# Power_supply.net
KiCad netlist of a schematic drawn in Altium Designer
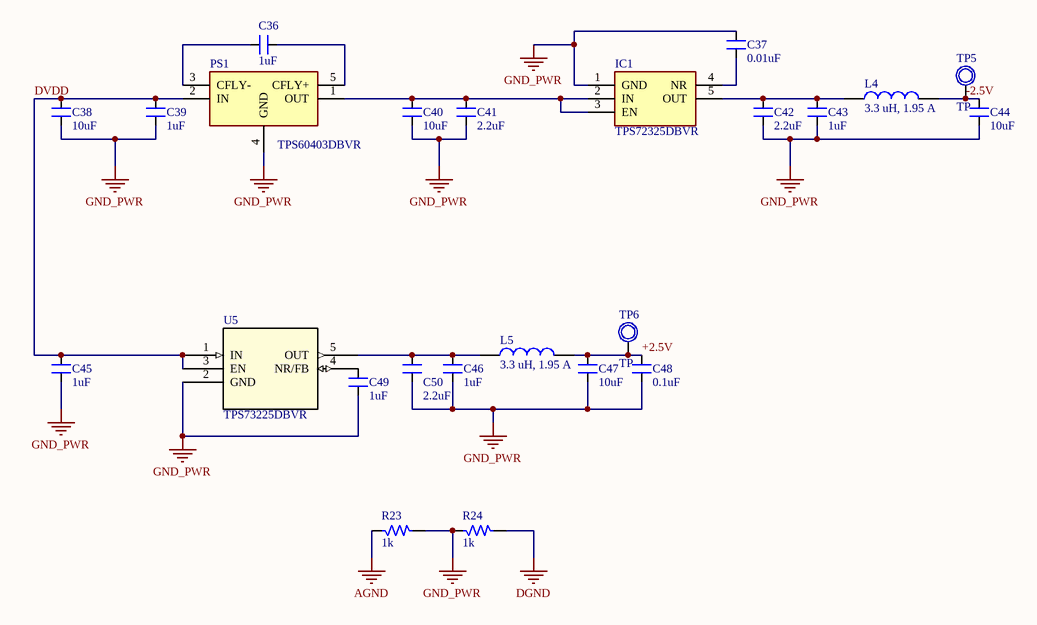
[diagram p0: Power supply.SchDoc]

(export (version "E")
  (design (tool "Eeschema 10.0.6"))
  (components
    (comp (ref "C36")
      (value "1uF")
      (footprint "SM-0805")
      (description "Cap SMD")
      (libsource (lib "VioletofSun") (part "CM"))
    )
    (comp (ref "C37")
      (value "0.01uF")
      (footprint "SM-0805")
      (description "Cap SMD")
      (libsource (lib "VioletofSun") (part "CM"))
    )
    (comp (ref "C38")
      (value "10uF")
      (footprint "SM-0805")
      (description "Cap SMD")
      (libsource (lib "VioletofSun") (part "CM"))
    )
    (comp (ref "C39")
      (value "1uF")
      (footprint "SM-0805")
      (description "Cap SMD")
      (libsource (lib "VioletofSun") (part "CM"))
    )
    (comp (ref "C40")
      (value "10uF")
      (footprint "SM-0805")
      (description "Cap SMD")
      (libsource (lib "VioletofSun") (part "CM"))
    )
    (comp (ref "C41")
      (value "2.2uF")
      (footprint "SM-0805")
      (description "Cap SMD")
      (libsource (lib "VioletofSun") (part "CM"))
    )
    (comp (ref "C42")
      (value "2.2uF")
      (footprint "SM-0805")
      (description "Cap SMD")
      (libsource (lib "VioletofSun") (part "CM"))
    )
    (comp (ref "C43")
      (value "1uF")
      (footprint "SM-0805")
      (description "Cap SMD")
      (libsource (lib "VioletofSun") (part "CM"))
    )
    (comp (ref "C44")
      (value "10uF")
      (footprint "SM-0805")
      (description "Cap SMD")
      (libsource (lib "VioletofSun") (part "CM"))
    )
    (comp (ref "C45")
      (value "1uF")
      (footprint "SM-0805")
      (description "Cap SMD")
      (libsource (lib "VioletofSun") (part "CM"))
    )
    (comp (ref "C46")
      (value "1uF")
      (footprint "SM-0805")
      (description "Cap SMD")
      (libsource (lib "VioletofSun") (part "CM"))
    )
    (comp (ref "C47")
      (value "10uF")
      (footprint "SM-0805")
      (description "Cap SMD")
      (libsource (lib "VioletofSun") (part "CM"))
    )
    (comp (ref "C48")
      (value "0.1uF")
      (footprint "SM-0805")
      (description "Cap SMD")
      (libsource (lib "VioletofSun") (part "CM"))
    )
    (comp (ref "C49")
      (value "1uF")
      (footprint "SM-0805")
      (description "Cap SMD")
      (libsource (lib "VioletofSun") (part "CM"))
    )
    (comp (ref "C50")
      (value "2.2uF")
      (footprint "SM-0805")
      (description "Cap SMD")
      (libsource (lib "VioletofSun") (part "CM"))
    )
    (comp (ref "IC1")
      (value "TPS72325DBVR")
      (footprint "SamacSys:SOT95P280X145-5N")
      (description "Integrated Circuit")
      (fields (field (name "MOUSER PART NUMBER") "595-TPS72325DBVR"))
      (libsource (lib "*") (part "TPS72325DBVR"))
    )
    (comp (ref "L4")
      (value "3.3 uH, 1.95 A")
      (footprint "WE-TPC_4818")
      (description "SMT Shielded Tiny Power Inductor WE-TPC, size 4818, 3.3 uH, 1.95 A")
      (fields (field (name "PART NUMBER") "744042003") (field (name "PUBLISHER") "Wurth Elektronik"))
      (libsource (lib "ALTIUM-WE-TPC-rev18a") (part "744042003"))
    )
    (comp (ref "L5")
      (value "3.3 uH, 1.95 A")
      (footprint "WE-TPC_4818")
      (description "SMT Shielded Tiny Power Inductor WE-TPC, size 4818, 3.3 uH, 1.95 A")
      (fields (field (name "PART NUMBER") "744042003") (field (name "PUBLISHER") "Wurth Elektronik"))
      (libsource (lib "ALTIUM-WE-TPC-rev18a") (part "744042003"))
    )
    (comp (ref "PS1")
      (value "TPS60403DBVR")
      (footprint "SamacSys:SOT95P280X145-5N")
      (description "Power Supply")
      (fields (field (name "MOUSER PART NUMBER") "595-TPS60403DBVR"))
      (libsource (lib "SamacSys") (part "TPS60403DBVR"))
    )
    (comp (ref "R23")
      (value "1k")
      (footprint "SM-0805")
      (description "Resistor 1/4W")
      (libsource (lib "VioletofSun") (part "R"))
    )
    (comp (ref "R24")
      (value "1k")
      (footprint "SM-0805")
      (description "Resistor 1/4W")
      (libsource (lib "VioletofSun") (part "R"))
    )
    (comp (ref "TP5")
      (value "TP")
      (footprint "VioletofSun:TP1")
      (description "Test Point")
      (libsource (lib "VioletofSun") (part "TP1"))
    )
    (comp (ref "TP6")
      (value "TP")
      (footprint "VioletofSun:TP1")
      (description "Test Point")
      (libsource (lib "VioletofSun") (part "TP1"))
    )
    (comp (ref "U5")
      (value "TPS73225DBVR")
      (footprint "DBV5")
      (description "No Description Available")
      (fields
        (field (name "MANUFACTURER") "Texas Instruments")
        (field (name "COPYRIGHT") "Copyright (C) 2018 Accelerated Designs. All rights reserved")
      )
      (libsource (lib "TPS73225DBVR") (part "TPS73225DBVR"))
    )
  )
  (nets
    (net (code "1") (name "/+2.5V") (class "Default")
      (node (ref "C47") (pin "2") (pinfunction "2_2") (pintype "passive"))
      (node (ref "C48") (pin "2") (pinfunction "2_2") (pintype "passive"))
      (node (ref "L5") (pin "2") (pinfunction "2_2") (pintype "passive"))
      (node (ref "TP6") (pin "1") (pinfunction "1_1") (pintype "passive"))
    )
    (net (code "2") (name "/-2.5V") (class "Default")
      (node (ref "C44") (pin "2") (pinfunction "2_2") (pintype "passive"))
      (node (ref "L4") (pin "2") (pinfunction "2_2") (pintype "passive"))
      (node (ref "TP5") (pin "1") (pinfunction "1_1") (pintype "passive"))
    )
    (net (code "3") (name "/DVDD") (class "Default")
      (node (ref "C38") (pin "2") (pinfunction "2_2") (pintype "passive"))
      (node (ref "C39") (pin "2") (pinfunction "2_2") (pintype "passive"))
      (node (ref "C45") (pin "2") (pinfunction "2_2") (pintype "passive"))
      (node (ref "PS1") (pin "2") (pinfunction "IN_2") (pintype "passive"))
      (node (ref "U5") (pin "1") (pinfunction "IN_1") (pintype "input"))
      (node (ref "U5") (pin "3") (pinfunction "EN_3") (pintype "passive"))
    )
    (net (code "4") (name "AGND") (class "Default")
      (node (ref "R23") (pin "1") (pinfunction "1_1") (pintype "passive"))
    )
    (net (code "5") (name "DGND") (class "Default")
      (node (ref "R24") (pin "2") (pinfunction "2_2") (pintype "passive"))
    )
    (net (code "6") (name "GND_PWR") (class "Default")
      (node (ref "C37") (pin "2") (pinfunction "2_2") (pintype "passive"))
      (node (ref "C38") (pin "1") (pinfunction "1_1") (pintype "passive"))
      (node (ref "C39") (pin "1") (pinfunction "1_1") (pintype "passive"))
      (node (ref "C40") (pin "1") (pinfunction "1_1") (pintype "passive"))
      (node (ref "C41") (pin "1") (pinfunction "1_1") (pintype "passive"))
      (node (ref "C42") (pin "1") (pinfunction "1_1") (pintype "passive"))
      (node (ref "C43") (pin "1") (pinfunction "1_1") (pintype "passive"))
      (node (ref "C44") (pin "1") (pinfunction "1_1") (pintype "passive"))
      (node (ref "C45") (pin "1") (pinfunction "1_1") (pintype "passive"))
      (node (ref "C46") (pin "1") (pinfunction "1_1") (pintype "passive"))
      (node (ref "C47") (pin "1") (pinfunction "1_1") (pintype "passive"))
      (node (ref "C48") (pin "1") (pinfunction "1_1") (pintype "passive"))
      (node (ref "C49") (pin "1") (pinfunction "1_1") (pintype "passive"))
      (node (ref "C50") (pin "1") (pinfunction "1_1") (pintype "passive"))
      (node (ref "IC1") (pin "1") (pinfunction "GND_1") (pintype "passive"))
      (node (ref "PS1") (pin "4") (pinfunction "GND_4") (pintype "passive"))
      (node (ref "R23") (pin "2") (pinfunction "2_2") (pintype "passive"))
      (node (ref "R24") (pin "1") (pinfunction "1_1") (pintype "passive"))
      (node (ref "U5") (pin "2") (pinfunction "GND_2") (pintype "power_in"))
    )
    (net (code "7") (name "Net-(IC1-EN)") (class "Default")
      (node (ref "C40") (pin "2") (pinfunction "2_2") (pintype "passive"))
      (node (ref "C41") (pin "2") (pinfunction "2_2") (pintype "passive"))
      (node (ref "IC1") (pin "2") (pinfunction "IN_2") (pintype "passive"))
      (node (ref "IC1") (pin "3") (pinfunction "EN_3") (pintype "passive"))
      (node (ref "PS1") (pin "1") (pinfunction "OUT_1") (pintype "passive"))
    )
    (net (code "8") (name "Net-(IC1-NR)") (class "Default")
      (node (ref "C37") (pin "1") (pinfunction "1_1") (pintype "passive"))
      (node (ref "IC1") (pin "4") (pinfunction "NR_4") (pintype "passive"))
    )
    (net (code "9") (name "Net-(IC1-OUT)") (class "Default")
      (node (ref "C42") (pin "2") (pinfunction "2_2") (pintype "passive"))
      (node (ref "C43") (pin "2") (pinfunction "2_2") (pintype "passive"))
      (node (ref "IC1") (pin "5") (pinfunction "OUT_5") (pintype "passive"))
      (node (ref "L4") (pin "1") (pinfunction "1_1") (pintype "passive"))
    )
    (net (code "10") (name "Net-(PS1-CFLY+)") (class "Default")
      (node (ref "C36") (pin "1") (pinfunction "1_1") (pintype "passive"))
      (node (ref "PS1") (pin "5") (pinfunction "CFLY+_5") (pintype "passive"))
    )
    (net (code "11") (name "Net-(PS1-CFLY-)") (class "Default")
      (node (ref "C36") (pin "2") (pinfunction "2_2") (pintype "passive"))
      (node (ref "PS1") (pin "3") (pinfunction "CFLY-_3") (pintype "passive"))
    )
    (net (code "12") (name "Net-(U5-NR{slash}FB)") (class "Default")
      (node (ref "C49") (pin "2") (pinfunction "2_2") (pintype "passive"))
      (node (ref "U5") (pin "4") (pinfunction "NR/FB_4") (pintype "bidirectional"))
    )
    (net (code "13") (name "Net-(U5-OUT)") (class "Default")
      (node (ref "C46") (pin "2") (pinfunction "2_2") (pintype "passive"))
      (node (ref "C50") (pin "2") (pinfunction "2_2") (pintype "passive"))
      (node (ref "L5") (pin "1") (pinfunction "1_1") (pintype "passive"))
      (node (ref "U5") (pin "5") (pinfunction "OUT_5") (pintype "output"))
    )
  )
)
